# DPPXHK_10CL010_FPGA.net
KiCad netlist of a schematic drawn in Altium Designer
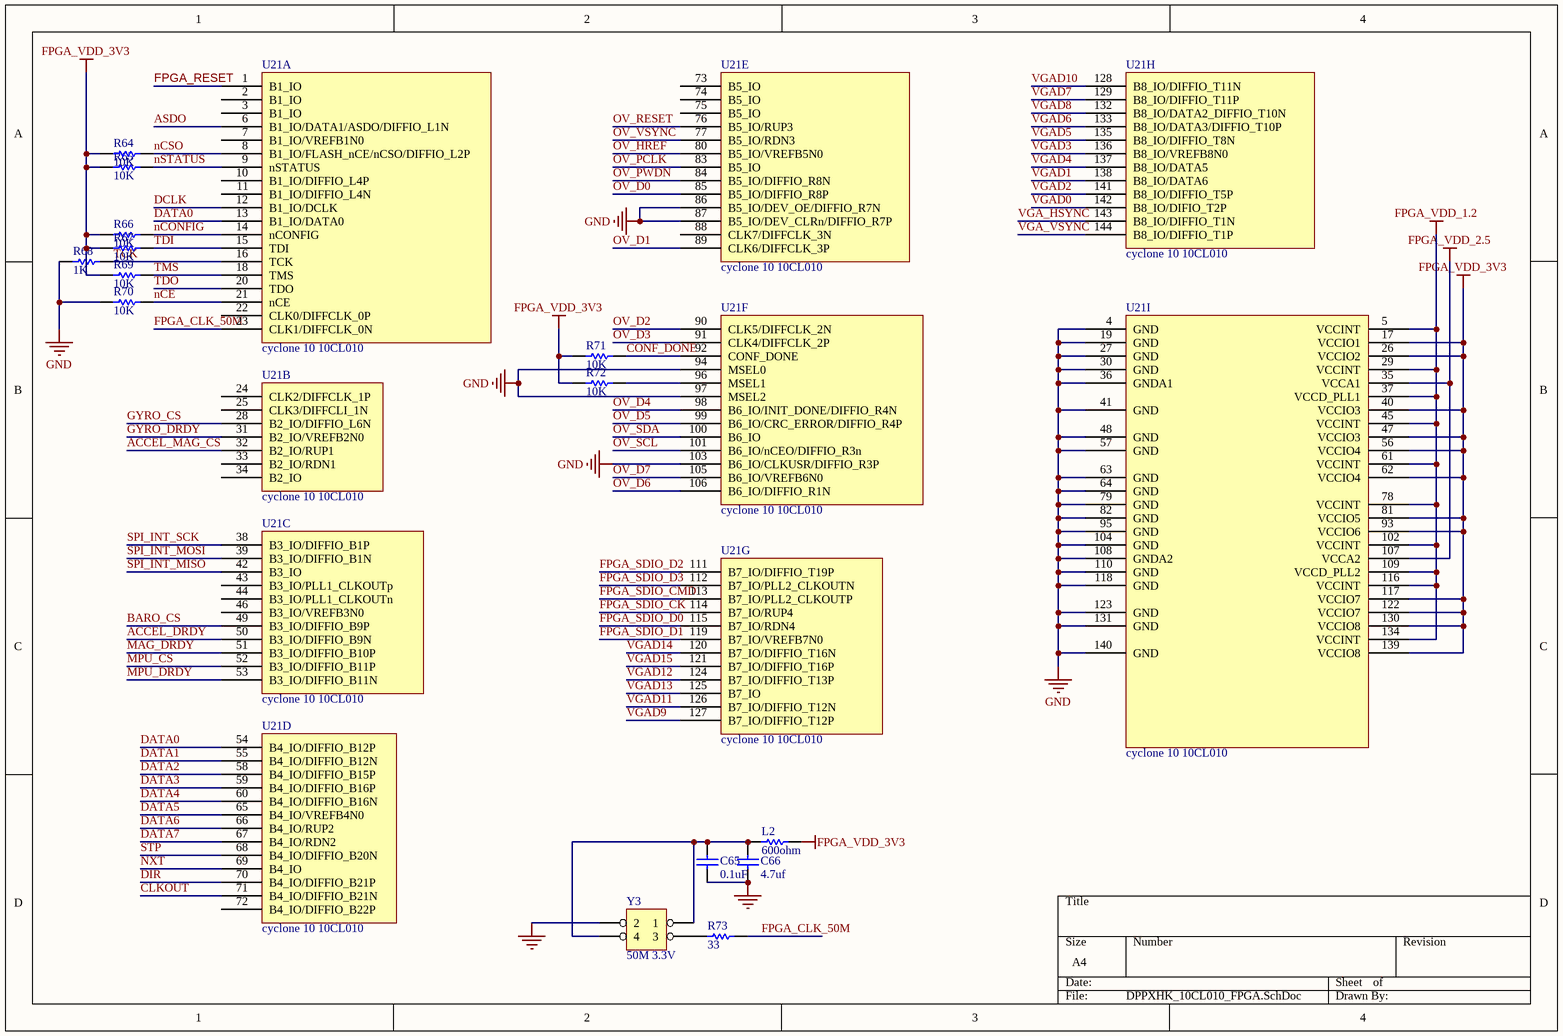
[diagram p0: DPPXHK_10CL010_FPGA.SchDoc]

(export (version "E")
  (design (tool "Eeschema 10.0.6"))
  (components
    (comp (ref "C65")
      (value "0.1uF")
      (footprint "LC0402")
      (description "Capacitor (Semiconductor SIM Model)")
      (fields (field (name "Comment") "104") (field (name "PUBLISHER") "Altium Limited"))
      (libsource (lib "*") (part "Cap Semi"))
    )
    (comp (ref "C66")
      (value "4.7uf")
      (footprint "LC0402")
      (description "Capacitor (Semiconductor SIM Model)")
      (fields (field (name "Comment") "105") (field (name "PUBLISHER") "Altium Limited"))
      (libsource (lib "*") (part "Cap Semi"))
    )
    (comp (ref "L2")
      (value "600ohm")
      (footprint "0402R")
      (description "Resistor")
      (fields
        (field (name "MANUFACTURER") "Generic Components")
        (field (name "Comment") "10K")
        (field (name "PUBLISHER") "Altium Hobart Technology Centre")
      )
      (libsource (lib "*") (part "Res1"))
    )
    (comp (ref "R64")
      (value "10K")
      (footprint "0402R")
      (description "Resistor")
      (fields
        (field (name "MANUFACTURER") "Generic Components")
        (field (name "PUBLISHER") "Altium Hobart Technology Centre")
      )
      (libsource (lib "*") (part "Res1"))
    )
    (comp (ref "R65")
      (value "10K")
      (footprint "0402R")
      (description "Resistor")
      (fields
        (field (name "MANUFACTURER") "Generic Components")
        (field (name "PUBLISHER") "Altium Hobart Technology Centre")
      )
      (libsource (lib "*") (part "Res1"))
    )
    (comp (ref "R66")
      (value "10K")
      (footprint "0402R")
      (description "Resistor")
      (fields
        (field (name "MANUFACTURER") "Generic Components")
        (field (name "PUBLISHER") "Altium Hobart Technology Centre")
      )
      (libsource (lib "*") (part "Res1"))
    )
    (comp (ref "R67")
      (value "10K")
      (footprint "0402R")
      (description "Resistor")
      (fields
        (field (name "MANUFACTURER") "Generic Components")
        (field (name "PUBLISHER") "Altium Hobart Technology Centre")
      )
      (libsource (lib "*") (part "Res1"))
    )
    (comp (ref "R68")
      (value "1K")
      (footprint "0402R")
      (description "Resistor")
      (fields
        (field (name "MANUFACTURER") "Generic Components")
        (field (name "Comment") "10K")
        (field (name "PUBLISHER") "Altium Hobart Technology Centre")
      )
      (libsource (lib "*") (part "Res1"))
    )
    (comp (ref "R69")
      (value "10K")
      (footprint "0402R")
      (description "Resistor")
      (fields
        (field (name "MANUFACTURER") "Generic Components")
        (field (name "PUBLISHER") "Altium Hobart Technology Centre")
      )
      (libsource (lib "*") (part "Res1"))
    )
    (comp (ref "R70")
      (value "10K")
      (footprint "0402R")
      (description "Resistor")
      (fields
        (field (name "MANUFACTURER") "Generic Components")
        (field (name "PUBLISHER") "Altium Hobart Technology Centre")
      )
      (libsource (lib "*") (part "Res1"))
    )
    (comp (ref "R71")
      (value "10K")
      (footprint "0402R")
      (description "Resistor")
      (fields
        (field (name "MANUFACTURER") "Generic Components")
        (field (name "PUBLISHER") "Altium Hobart Technology Centre")
      )
      (libsource (lib "*") (part "Res1"))
    )
    (comp (ref "R72")
      (value "10K")
      (footprint "0402R")
      (description "Resistor")
      (fields
        (field (name "MANUFACTURER") "Generic Components")
        (field (name "PUBLISHER") "Altium Hobart Technology Centre")
      )
      (libsource (lib "*") (part "Res1"))
    )
    (comp (ref "R73")
      (value "33")
      (footprint "0402R")
      (description "Resistor")
      (fields
        (field (name "MANUFACTURER") "Generic Components")
        (field (name "Comment") "10K")
        (field (name "PUBLISHER") "Altium Hobart Technology Centre")
      )
      (libsource (lib "*") (part "Res1"))
    )
    (comp (ref "U21") (value "cyclone 10 10CL010") (libsource (lib "PXHK") (part "10CL010E144")))
    (comp (ref "Y3")
      (value "50M 3.3V")
      (footprint "OSCILLATOR-3.2X2.5")
      (libsource (lib "*") (part "HEADER 2X2"))
    )
  )
  (nets
    (net (code "1") (name "/ACCEL_DRDY") (class "Default")
      (node (ref "U21") (pin "50") (pinfunction "B3_IO/DIFFIO_B9N_50") (pintype "passive"))
    )
    (net (code "2") (name "/ACCEL_MAG_CS") (class "Default")
      (node (ref "U21") (pin "32") (pinfunction "B2_IO/RUP1_32") (pintype "passive"))
    )
    (net (code "3") (name "/ASDO") (class "Default")
      (node (ref "U21") (pin "6") (pinfunction "B1_IO/DATA1/ASDO/DIFFIO_L1N_6") (pintype "passive"))
    )
    (net (code "4") (name "/BARO_CS") (class "Default")
      (node (ref "U21") (pin "49") (pinfunction "B3_IO/DIFFIO_B9P_49") (pintype "passive"))
    )
    (net (code "5") (name "/CLKOUT") (class "Default")
      (node (ref "U21") (pin "71") (pinfunction "B4_IO/DIFFIO_B21N_71") (pintype "passive"))
    )
    (net (code "6") (name "/CONF_DONE") (class "Default")
      (node (ref "R71") (pin "2") (pinfunction "2_2") (pintype "passive"))
      (node (ref "U21") (pin "92") (pinfunction "CONF_DONE_92") (pintype "passive"))
    )
    (net (code "7") (name "/DATA0") (class "Default")
      (node (ref "U21") (pin "13") (pinfunction "B1_IO/DATA0_13") (pintype "passive"))
      (node (ref "U21") (pin "54") (pinfunction "B4_IO/DIFFIO_B12P_54") (pintype "passive"))
    )
    (net (code "8") (name "/DATA1") (class "Default")
      (node (ref "U21") (pin "55") (pinfunction "B4_IO/DIFFIO_B12N_55") (pintype "passive"))
    )
    (net (code "9") (name "/DATA2") (class "Default")
      (node (ref "U21") (pin "58") (pinfunction "B4_IO/DIFFIO_B15P_58") (pintype "passive"))
    )
    (net (code "10") (name "/DATA3") (class "Default")
      (node (ref "U21") (pin "59") (pinfunction "B4_IO/DIFFIO_B16P_59") (pintype "passive"))
    )
    (net (code "11") (name "/DATA4") (class "Default")
      (node (ref "U21") (pin "60") (pinfunction "B4_IO/DIFFIO_B16N_60") (pintype "passive"))
    )
    (net (code "12") (name "/DATA5") (class "Default")
      (node (ref "U21") (pin "65") (pinfunction "B4_IO/VREFB4N0_65") (pintype "passive"))
    )
    (net (code "13") (name "/DATA6") (class "Default")
      (node (ref "U21") (pin "66") (pinfunction "B4_IO/RUP2_66") (pintype "passive"))
    )
    (net (code "14") (name "/DATA7") (class "Default")
      (node (ref "U21") (pin "67") (pinfunction "B4_IO/RDN2_67") (pintype "passive"))
    )
    (net (code "15") (name "/DCLK") (class "Default")
      (node (ref "U21") (pin "12") (pinfunction "B1_IO/DCLK_12") (pintype "passive"))
    )
    (net (code "16") (name "/DIR") (class "Default")
      (node (ref "U21") (pin "70") (pinfunction "B4_IO/DIFFIO_B21P_70") (pintype "passive"))
    )
    (net (code "17") (name "/FPGA_CLK_50M") (class "Default")
      (node (ref "R73") (pin "2") (pinfunction "2_2") (pintype "passive"))
      (node (ref "U21") (pin "23") (pinfunction "CLK1/DIFFCLK_0N_23") (pintype "passive"))
    )
    (net (code "18") (name "/FPGA_RESET") (class "Default")
      (node (ref "U21") (pin "1") (pinfunction "B1_IO_1") (pintype "passive"))
    )
    (net (code "19") (name "/FPGA_SDIO_CK") (class "Default")
      (node (ref "U21") (pin "114") (pinfunction "B7_IO/RUP4_114") (pintype "passive"))
    )
    (net (code "20") (name "/FPGA_SDIO_CMD") (class "Default")
      (node (ref "U21") (pin "113") (pinfunction "B7_IO/PLL2_CLKOUTP_113") (pintype "passive"))
    )
    (net (code "21") (name "/FPGA_SDIO_D0") (class "Default")
      (node (ref "U21") (pin "115") (pinfunction "B7_IO/RDN4_115") (pintype "passive"))
    )
    (net (code "22") (name "/FPGA_SDIO_D1") (class "Default")
      (node (ref "U21") (pin "119") (pinfunction "B7_IO/VREFB7N0_119") (pintype "passive"))
    )
    (net (code "23") (name "/FPGA_SDIO_D2") (class "Default")
      (node (ref "U21") (pin "111") (pinfunction "B7_IO/DIFFIO_T19P_111") (pintype "passive"))
    )
    (net (code "24") (name "/FPGA_SDIO_D3") (class "Default")
      (node (ref "U21") (pin "112") (pinfunction "B7_IO/PLL2_CLKOUTN_112") (pintype "passive"))
    )
    (net (code "25") (name "/GYRO_CS") (class "Default")
      (node (ref "U21") (pin "28") (pinfunction "B2_IO/DIFFIO_L6N_28") (pintype "passive"))
    )
    (net (code "26") (name "/GYRO_DRDY") (class "Default")
      (node (ref "U21") (pin "31") (pinfunction "B2_IO/VREFB2N0_31") (pintype "passive"))
    )
    (net (code "27") (name "/MAG_DRDY") (class "Default")
      (node (ref "U21") (pin "51") (pinfunction "B3_IO/DIFFIO_B10P_51") (pintype "passive"))
    )
    (net (code "28") (name "/MPU_CS") (class "Default")
      (node (ref "U21") (pin "52") (pinfunction "B3_IO/DIFFIO_B11P_52") (pintype "passive"))
    )
    (net (code "29") (name "/MPU_DRDY") (class "Default")
      (node (ref "U21") (pin "53") (pinfunction "B3_IO/DIFFIO_B11N_53") (pintype "passive"))
    )
    (net (code "30") (name "/NXT") (class "Default")
      (node (ref "U21") (pin "69") (pinfunction "B4_IO_69") (pintype "passive"))
    )
    (net (code "31") (name "/OV_D0") (class "Default")
      (node (ref "U21") (pin "85") (pinfunction "B5_IO/DIFFIO_R8P_85") (pintype "passive"))
    )
    (net (code "32") (name "/OV_D1") (class "Default")
      (node (ref "U21") (pin "89") (pinfunction "CLK6/DIFFCLK_3P_89") (pintype "passive"))
    )
    (net (code "33") (name "/OV_D2") (class "Default")
      (node (ref "U21") (pin "90") (pinfunction "CLK5/DIFFCLK_2N_90") (pintype "passive"))
    )
    (net (code "34") (name "/OV_D3") (class "Default")
      (node (ref "U21") (pin "91") (pinfunction "CLK4/DIFFCLK_2P_91") (pintype "passive"))
    )
    (net (code "35") (name "/OV_D4") (class "Default")
      (node (ref "U21") (pin "98") (pinfunction "B6_IO/INIT_DONE/DIFFIO_R4N_98") (pintype "passive"))
    )
    (net (code "36") (name "/OV_D5") (class "Default")
      (node (ref "U21") (pin "99") (pinfunction "B6_IO/CRC_ERROR/DIFFIO_R4P_99") (pintype "passive"))
    )
    (net (code "37") (name "/OV_D6") (class "Default")
      (node (ref "U21") (pin "106") (pinfunction "B6_IO/DIFFIO_R1N_106") (pintype "passive"))
    )
    (net (code "38") (name "/OV_D7") (class "Default")
      (node (ref "U21") (pin "105") (pinfunction "B6_IO/VREFB6N0_105") (pintype "passive"))
    )
    (net (code "39") (name "/OV_HREF") (class "Default")
      (node (ref "U21") (pin "80") (pinfunction "B5_IO/VREFB5N0_80") (pintype "passive"))
    )
    (net (code "40") (name "/OV_PCLK") (class "Default")
      (node (ref "U21") (pin "83") (pinfunction "B5_IO_83") (pintype "passive"))
    )
    (net (code "41") (name "/OV_PWDN") (class "Default")
      (node (ref "U21") (pin "84") (pinfunction "B5_IO/DIFFIO_R8N_84") (pintype "passive"))
    )
    (net (code "42") (name "/OV_RESET") (class "Default")
      (node (ref "U21") (pin "76") (pinfunction "B5_IO/RUP3_76") (pintype "passive"))
    )
    (net (code "43") (name "/OV_SCL") (class "Default")
      (node (ref "U21") (pin "101") (pinfunction "B6_IO/nCEO/DIFFIO_R3n_101") (pintype "passive"))
    )
    (net (code "44") (name "/OV_SDA") (class "Default")
      (node (ref "U21") (pin "100") (pinfunction "B6_IO_100") (pintype "passive"))
    )
    (net (code "45") (name "/OV_VSYNC") (class "Default")
      (node (ref "U21") (pin "77") (pinfunction "B5_IO/RDN3_77") (pintype "passive"))
    )
    (net (code "46") (name "/SPI_INT_MISO") (class "Default")
      (node (ref "U21") (pin "42") (pinfunction "B3_IO_42") (pintype "passive"))
    )
    (net (code "47") (name "/SPI_INT_MOSI") (class "Default")
      (node (ref "U21") (pin "39") (pinfunction "B3_IO/DIFFIO_B1N_39") (pintype "passive"))
    )
    (net (code "48") (name "/SPI_INT_SCK") (class "Default")
      (node (ref "U21") (pin "38") (pinfunction "B3_IO/DIFFIO_B1P_38") (pintype "passive"))
    )
    (net (code "49") (name "/STP") (class "Default")
      (node (ref "U21") (pin "68") (pinfunction "B4_IO/DIFFIO_B20N_68") (pintype "passive"))
    )
    (net (code "50") (name "/TCK") (class "Default")
      (node (ref "R68") (pin "2") (pinfunction "2_2") (pintype "passive"))
      (node (ref "U21") (pin "16") (pinfunction "TCK_16") (pintype "passive"))
    )
    (net (code "51") (name "/TDI") (class "Default")
      (node (ref "R67") (pin "2") (pinfunction "2_2") (pintype "passive"))
      (node (ref "U21") (pin "15") (pinfunction "TDI_15") (pintype "passive"))
    )
    (net (code "52") (name "/TDO") (class "Default")
      (node (ref "U21") (pin "20") (pinfunction "TDO_20") (pintype "passive"))
    )
    (net (code "53") (name "/TMS") (class "Default")
      (node (ref "R69") (pin "2") (pinfunction "2_2") (pintype "passive"))
      (node (ref "U21") (pin "18") (pinfunction "TMS_18") (pintype "passive"))
    )
    (net (code "54") (name "/VGAD0") (class "Default")
      (node (ref "U21") (pin "142") (pinfunction "B8_IO/DIFIO_T2P_142") (pintype "passive"))
    )
    (net (code "55") (name "/VGAD1") (class "Default")
      (node (ref "U21") (pin "138") (pinfunction "B8_IO/DATA6_138") (pintype "passive"))
    )
    (net (code "56") (name "/VGAD2") (class "Default")
      (node (ref "U21") (pin "141") (pinfunction "B8_IO/DIFFIO_T5P_141") (pintype "passive"))
    )
    (net (code "57") (name "/VGAD3") (class "Default")
      (node (ref "U21") (pin "136") (pinfunction "B8_IO/VREFB8N0_136") (pintype "passive"))
    )
    (net (code "58") (name "/VGAD4") (class "Default")
      (node (ref "U21") (pin "137") (pinfunction "B8_IO/DATA5_137") (pintype "passive"))
    )
    (net (code "59") (name "/VGAD5") (class "Default")
      (node (ref "U21") (pin "135") (pinfunction "B8_IO/DIFFIO_T8N_135") (pintype "passive"))
    )
    (net (code "60") (name "/VGAD6") (class "Default")
      (node (ref "U21") (pin "133") (pinfunction "B8_IO/DATA3/DIFFIO_T10P_133") (pintype "passive"))
    )
    (net (code "61") (name "/VGAD7") (class "Default")
      (node (ref "U21") (pin "129") (pinfunction "B8_IO/DIFFIO_T11P_129") (pintype "passive"))
    )
    (net (code "62") (name "/VGAD8") (class "Default")
      (node (ref "U21") (pin "132") (pinfunction "B8_IO/DATA2_DIFFIO_T10N_132") (pintype "passive"))
    )
    (net (code "63") (name "/VGAD9") (class "Default")
      (node (ref "U21") (pin "127") (pinfunction "B7_IO/DIFFIO_T12P_127") (pintype "passive"))
    )
    (net (code "64") (name "/VGAD10") (class "Default")
      (node (ref "U21") (pin "128") (pinfunction "B8_IO/DIFFIO_T11N_128") (pintype "passive"))
    )
    (net (code "65") (name "/VGAD11") (class "Default")
      (node (ref "U21") (pin "126") (pinfunction "B7_IO/DIFFIO_T12N_126") (pintype "passive"))
    )
    (net (code "66") (name "/VGAD12") (class "Default")
      (node (ref "U21") (pin "124") (pinfunction "B7_IO/DIFFIO_T13P_124") (pintype "passive"))
    )
    (net (code "67") (name "/VGAD13") (class "Default")
      (node (ref "U21") (pin "125") (pinfunction "B7_IO_125") (pintype "passive"))
    )
    (net (code "68") (name "/VGAD14") (class "Default")
      (node (ref "U21") (pin "120") (pinfunction "B7_IO/DIFFIO_T16N_120") (pintype "passive"))
    )
    (net (code "69") (name "/VGAD15") (class "Default")
      (node (ref "U21") (pin "121") (pinfunction "B7_IO/DIFFIO_T16P_121") (pintype "passive"))
    )
    (net (code "70") (name "/VGA_HSYNC") (class "Default")
      (node (ref "U21") (pin "143") (pinfunction "B8_IO/DIFFIO_T1N_143") (pintype "passive"))
    )
    (net (code "71") (name "/VGA_VSYNC") (class "Default")
      (node (ref "U21") (pin "144") (pinfunction "B8_IO/DIFFIO_T1P_144") (pintype "passive"))
    )
    (net (code "72") (name "/nCE") (class "Default")
      (node (ref "R70") (pin "2") (pinfunction "2_2") (pintype "passive"))
      (node (ref "U21") (pin "21") (pinfunction "nCE_21") (pintype "passive"))
    )
    (net (code "73") (name "/nCONFIG") (class "Default")
      (node (ref "R66") (pin "2") (pinfunction "2_2") (pintype "passive"))
      (node (ref "U21") (pin "14") (pinfunction "nCONFIG_14") (pintype "passive"))
    )
    (net (code "74") (name "/nCSO") (class "Default")
      (node (ref "R64") (pin "2") (pinfunction "2_2") (pintype "passive"))
      (node (ref "U21") (pin "8") (pinfunction "B1_IO/FLASH_nCE/nCSO/DIFFIO_L2P_8") (pintype "passive"))
    )
    (net (code "75") (name "/nSTATUS") (class "Default")
      (node (ref "R65") (pin "2") (pinfunction "2_2") (pintype "passive"))
      (node (ref "U21") (pin "9") (pinfunction "nSTATUS_9") (pintype "passive"))
    )
    (net (code "76") (name "FPGA_VDD_1.2") (class "Default")
      (node (ref "U21") (pin "102") (pinfunction "VCCINT_102") (pintype "passive"))
      (node (ref "U21") (pin "109") (pinfunction "VCCD_PLL2_109") (pintype "passive"))
      (node (ref "U21") (pin "116") (pinfunction "VCCINT_116") (pintype "passive"))
      (node (ref "U21") (pin "134") (pinfunction "VCCINT_134") (pintype "passive"))
      (node (ref "U21") (pin "29") (pinfunction "VCCINT_29") (pintype "passive"))
      (node (ref "U21") (pin "37") (pinfunction "VCCD_PLL1_37") (pintype "passive"))
      (node (ref "U21") (pin "45") (pinfunction "VCCINT_45") (pintype "passive"))
      (node (ref "U21") (pin "5") (pinfunction "VCCINT_5") (pintype "passive"))
      (node (ref "U21") (pin "61") (pinfunction "VCCINT_61") (pintype "passive"))
      (node (ref "U21") (pin "78") (pinfunction "VCCINT_78") (pintype "passive"))
    )
    (net (code "77") (name "FPGA_VDD_2.5") (class "Default")
      (node (ref "U21") (pin "107") (pinfunction "VCCA2_107") (pintype "passive"))
      (node (ref "U21") (pin "35") (pinfunction "VCCA1_35") (pintype "passive"))
    )
    (net (code "78") (name "FPGA_VDD_3V3") (class "Default")
      (node (ref "L2") (pin "2") (pinfunction "2_2") (pintype "passive"))
      (node (ref "R64") (pin "1") (pinfunction "1_1") (pintype "passive"))
      (node (ref "R65") (pin "1") (pinfunction "1_1") (pintype "passive"))
      (node (ref "R66") (pin "1") (pinfunction "1_1") (pintype "passive"))
      (node (ref "R67") (pin "1") (pinfunction "1_1") (pintype "passive"))
      (node (ref "R69") (pin "1") (pinfunction "1_1") (pintype "passive"))
      (node (ref "R71") (pin "1") (pinfunction "1_1") (pintype "passive"))
      (node (ref "R72") (pin "1") (pinfunction "1_1") (pintype "passive"))
      (node (ref "U21") (pin "117") (pinfunction "VCCIO7_117") (pintype "passive"))
      (node (ref "U21") (pin "122") (pinfunction "VCCIO7_122") (pintype "passive"))
      (node (ref "U21") (pin "130") (pinfunction "VCCIO8_130") (pintype "passive"))
      (node (ref "U21") (pin "139") (pinfunction "VCCIO8_139") (pintype "passive"))
      (node (ref "U21") (pin "17") (pinfunction "VCCIO1_17") (pintype "passive"))
      (node (ref "U21") (pin "26") (pinfunction "VCCIO2_26") (pintype "passive"))
      (node (ref "U21") (pin "40") (pinfunction "VCCIO3_40") (pintype "passive"))
      (node (ref "U21") (pin "47") (pinfunction "VCCIO3_47") (pintype "passive"))
      (node (ref "U21") (pin "56") (pinfunction "VCCIO4_56") (pintype "passive"))
      (node (ref "U21") (pin "62") (pinfunction "VCCIO4_62") (pintype "passive"))
      (node (ref "U21") (pin "81") (pinfunction "VCCIO5_81") (pintype "passive"))
      (node (ref "U21") (pin "93") (pinfunction "VCCIO6_93") (pintype "passive"))
    )
    (net (code "79") (name "GND") (class "Default")
      (node (ref "C65") (pin "1") (pinfunction "1_1") (pintype "passive"))
      (node (ref "C66") (pin "1") (pinfunction "1_1") (pintype "passive"))
      (node (ref "R68") (pin "1") (pinfunction "1_1") (pintype "passive"))
      (node (ref "R70") (pin "1") (pinfunction "1_1") (pintype "passive"))
      (node (ref "U21") (pin "103") (pinfunction "B6_IO/CLKUSR/DIFFIO_R3P_103") (pintype "passive"))
      (node (ref "U21") (pin "104") (pinfunction "GND_104") (pintype "passive"))
      (node (ref "U21") (pin "108") (pinfunction "GNDA2_108") (pintype "passive"))
      (node (ref "U21") (pin "110") (pinfunction "GND_110") (pintype "passive"))
      (node (ref "U21") (pin "118") (pinfunction "GND_118") (pintype "passive"))
      (node (ref "U21") (pin "123") (pinfunction "GND_123") (pintype "passive"))
      (node (ref "U21") (pin "131") (pinfunction "GND_131") (pintype "passive"))
      (node (ref "U21") (pin "140") (pinfunction "GND_140") (pintype "passive"))
      (node (ref "U21") (pin "19") (pinfunction "GND_19") (pintype "passive"))
      (node (ref "U21") (pin "27") (pinfunction "GND_27") (pintype "passive"))
      (node (ref "U21") (pin "30") (pinfunction "GND_30") (pintype "passive"))
      (node (ref "U21") (pin "36") (pinfunction "GNDA1_36") (pintype "passive"))
      (node (ref "U21") (pin "4") (pinfunction "GND_4") (pintype "passive"))
      (node (ref "U21") (pin "41") (pinfunction "GND_41") (pintype "passive"))
      (node (ref "U21") (pin "48") (pinfunction "GND_48") (pintype "passive"))
      (node (ref "U21") (pin "57") (pinfunction "GND_57") (pintype "passive"))
      (node (ref "U21") (pin "63") (pinfunction "GND_63") (pintype "passive"))
      (node (ref "U21") (pin "64") (pinfunction "GND_64") (pintype "passive"))
      (node (ref "U21") (pin "79") (pinfunction "GND_79") (pintype "passive"))
      (node (ref "U21") (pin "82") (pinfunction "GND_82") (pintype "passive"))
      (node (ref "U21") (pin "86") (pinfunction "B5_IO/DEV_OE/DIFFIO_R7N_86") (pintype "passive"))
      (node (ref "U21") (pin "87") (pinfunction "B5_IO/DEV_CLRn/DIFFIO_R7P_87") (pintype "passive"))
      (node (ref "U21") (pin "94") (pinfunction "MSEL0_94") (pintype "passive"))
      (node (ref "U21") (pin "95") (pinfunction "GND_95") (pintype "passive"))
      (node (ref "U21") (pin "97") (pinfunction "MSEL2_97") (pintype "passive"))
      (node (ref "Y3") (pin "2") (pinfunction "2_2") (pintype "passive"))
    )
    (net (code "80") (name "Net-(C65-Pad2)") (class "Default")
      (node (ref "C65") (pin "2") (pinfunction "2_2") (pintype "passive"))
      (node (ref "C66") (pin "2") (pinfunction "2_2") (pintype "passive"))
      (node (ref "L2") (pin "1") (pinfunction "1_1") (pintype "passive"))
      (node (ref "Y3") (pin "1") (pinfunction "1_1") (pintype "passive"))
      (node (ref "Y3") (pin "4") (pinfunction "4_4") (pintype "passive"))
    )
    (net (code "81") (name "Net-(R73-Pad1)") (class "Default")
      (node (ref "R73") (pin "1") (pinfunction "1_1") (pintype "passive"))
      (node (ref "Y3") (pin "3") (pinfunction "3_3") (pintype "passive"))
    )
    (net (code "82") (name "Net-(U21F-MSEL1)") (class "Default")
      (node (ref "R72") (pin "2") (pinfunction "2_2") (pintype "passive"))
      (node (ref "U21") (pin "96") (pinfunction "MSEL1_96") (pintype "passive"))
    )
    (net (code "83") (name "unconnected-(U21A-B1_IO-Pad2)") (class "Default")
      (node (ref "U21") (pin "2") (pinfunction "B1_IO_2") (pintype "passive"))
    )
    (net (code "84") (name "unconnected-(U21A-B1_IO-Pad3)") (class "Default")
      (node (ref "U21") (pin "3") (pinfunction "B1_IO_3") (pintype "passive"))
    )
    (net (code "85") (name "unconnected-(U21A-B1_IO{slash}DIFFIO_L4N-Pad11)") (class "Default")
      (node (ref "U21") (pin "11") (pinfunction "B1_IO/DIFFIO_L4N_11") (pintype "passive"))
    )
    (net (code "86") (name "unconnected-(U21A-B1_IO{slash}DIFFIO_L4P-Pad10)") (class "Default")
      (node (ref "U21") (pin "10") (pinfunction "B1_IO/DIFFIO_L4P_10") (pintype "passive"))
    )
    (net (code "87") (name "unconnected-(U21A-B1_IO{slash}VREFB1N0-Pad7)") (class "Default")
      (node (ref "U21") (pin "7") (pinfunction "B1_IO/VREFB1N0_7") (pintype "passive"))
    )
    (net (code "88") (name "unconnected-(U21A-CLK0{slash}DIFFCLK_0P-Pad22)") (class "Default")
      (node (ref "U21") (pin "22") (pinfunction "CLK0/DIFFCLK_0P_22") (pintype "passive"))
    )
    (net (code "89") (name "unconnected-(U21B-B2_IO-Pad34)") (class "Default")
      (node (ref "U21") (pin "34") (pinfunction "B2_IO_34") (pintype "passive"))
    )
    (net (code "90") (name "unconnected-(U21B-B2_IO{slash}RDN1-Pad33)") (class "Default")
      (node (ref "U21") (pin "33") (pinfunction "B2_IO/RDN1_33") (pintype "passive"))
    )
    (net (code "91") (name "unconnected-(U21B-CLK2{slash}DIFFCLK_1P-Pad24)") (class "Default")
      (node (ref "U21") (pin "24") (pinfunction "CLK2/DIFFCLK_1P_24") (pintype "passive"))
    )
    (net (code "92") (name "unconnected-(U21B-CLK3{slash}DIFFCLI_1N-Pad25)") (class "Default")
      (node (ref "U21") (pin "25") (pinfunction "CLK3/DIFFCLI_1N_25") (pintype "passive"))
    )
    (net (code "93") (name "unconnected-(U21C-B3_IO{slash}PLL1_CLKOUTn-Pad44)") (class "Default")
      (node (ref "U21") (pin "44") (pinfunction "B3_IO/PLL1_CLKOUTn_44") (pintype "passive"))
    )
    (net (code "94") (name "unconnected-(U21C-B3_IO{slash}PLL1_CLKOUTp-Pad43)") (class "Default")
      (node (ref "U21") (pin "43") (pinfunction "B3_IO/PLL1_CLKOUTp_43") (pintype "passive"))
    )
    (net (code "95") (name "unconnected-(U21C-B3_IO{slash}VREFB3N0-Pad46)") (class "Default")
      (node (ref "U21") (pin "46") (pinfunction "B3_IO/VREFB3N0_46") (pintype "passive"))
    )
    (net (code "96") (name "unconnected-(U21D-B4_IO{slash}DIFFIO_B22P-Pad72)") (class "Default")
      (node (ref "U21") (pin "72") (pinfunction "B4_IO/DIFFIO_B22P_72") (pintype "passive"))
    )
    (net (code "97") (name "unconnected-(U21E-B5_IO-Pad73)") (class "Default")
      (node (ref "U21") (pin "73") (pinfunction "B5_IO_73") (pintype "passive"))
    )
    (net (code "98") (name "unconnected-(U21E-B5_IO-Pad74)") (class "Default")
      (node (ref "U21") (pin "74") (pinfunction "B5_IO_74") (pintype "passive"))
    )
    (net (code "99") (name "unconnected-(U21E-B5_IO-Pad75)") (class "Default")
      (node (ref "U21") (pin "75") (pinfunction "B5_IO_75") (pintype "passive"))
    )
    (net (code "100") (name "unconnected-(U21E-CLK7{slash}DIFFCLK_3N-Pad88)") (class "Default")
      (node (ref "U21") (pin "88") (pinfunction "CLK7/DIFFCLK_3N_88") (pintype "passive"))
    )
  )
)
